# Sheet1.net
KiCad netlist of a schematic drawn in Altium Designer
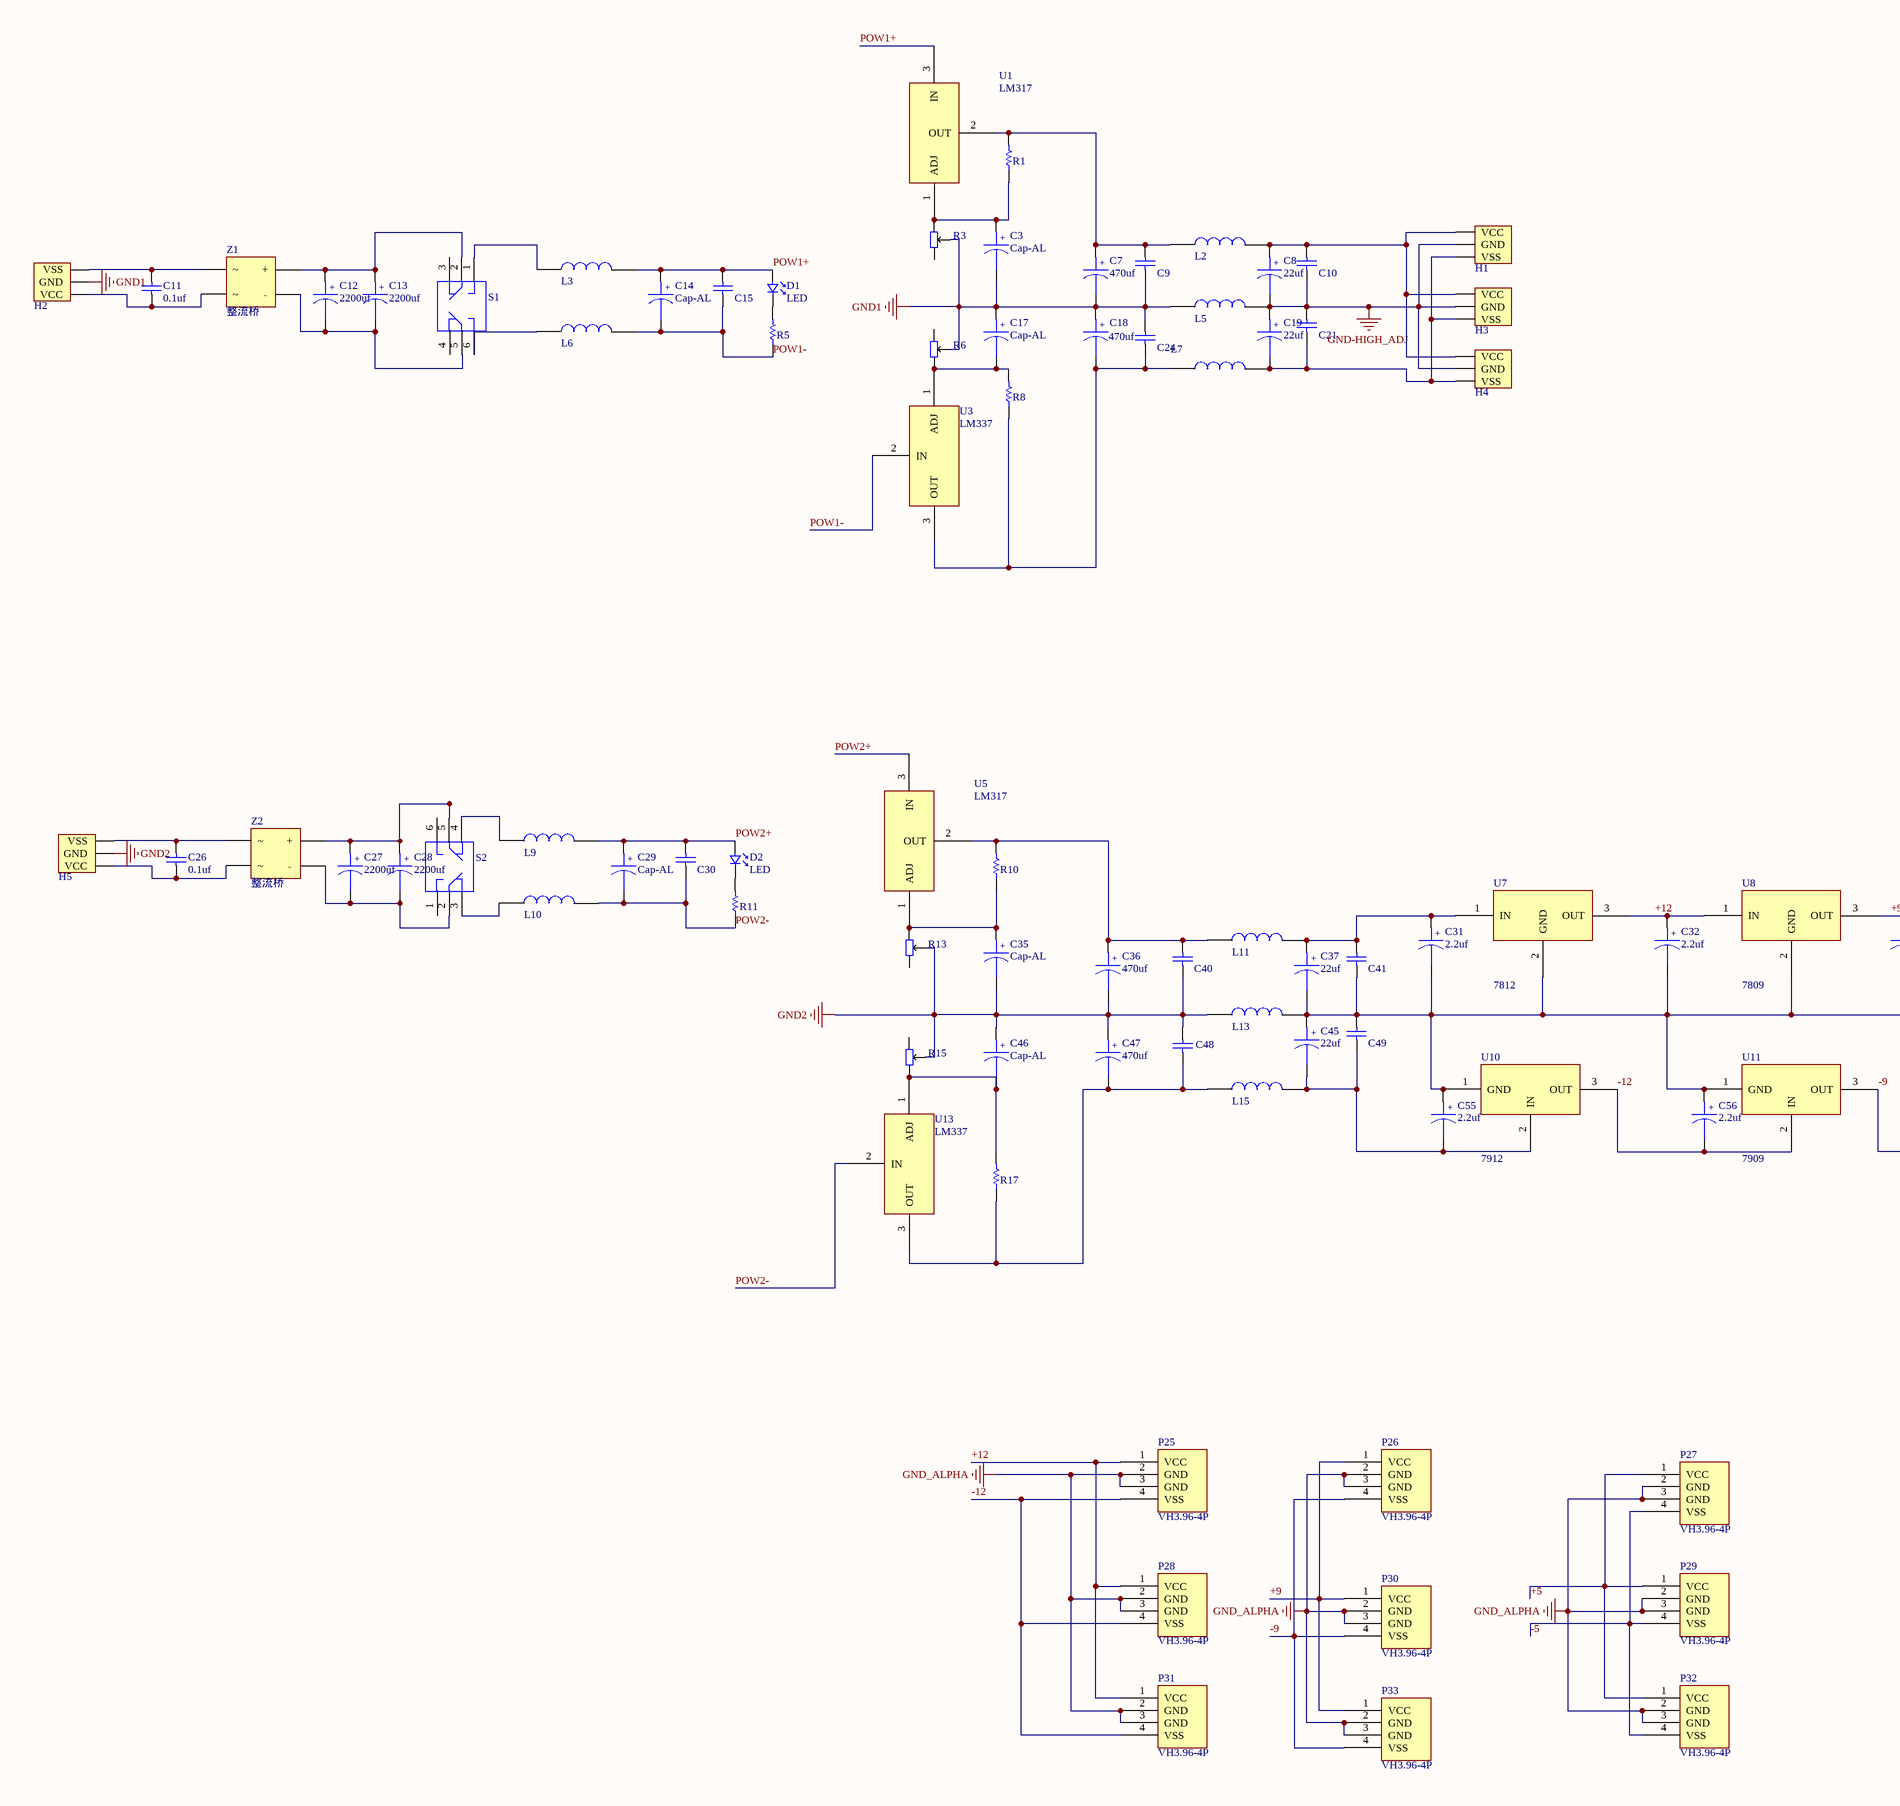
[diagram p0: Sheet1.SchDoc, left]
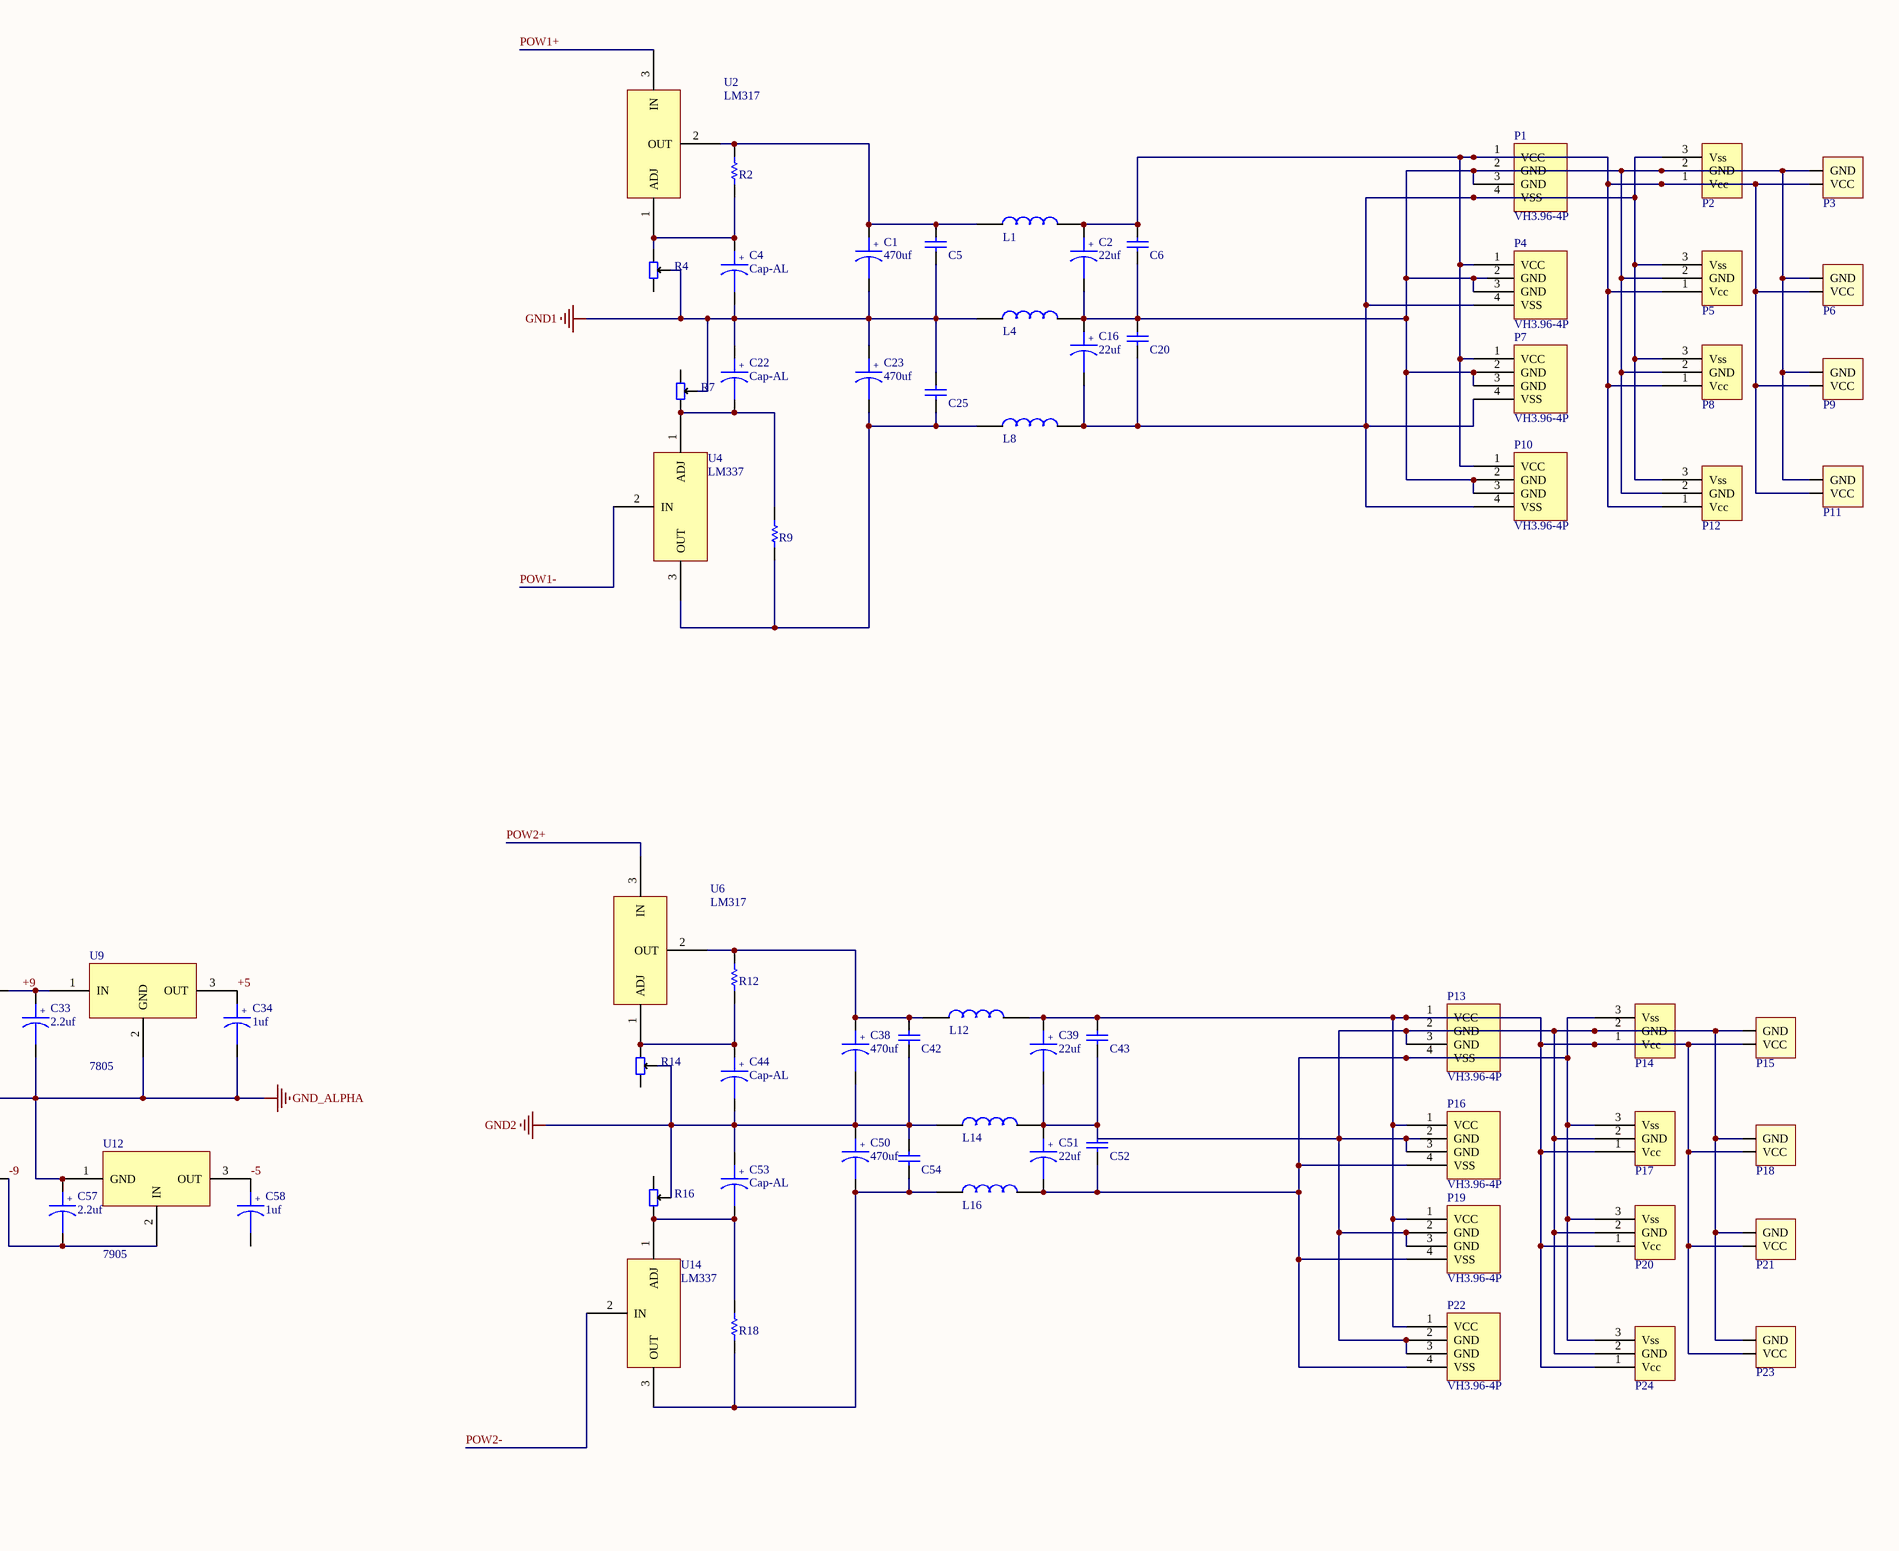
[diagram p1: Sheet1.SchDoc, right]

(export (version "E")
  (design (tool "Eeschema 10.0.6"))
  (components
    (comp (ref "C1") (value "470uf") (footprint "CD-5mm") (libsource (lib "电源") (part "Cap-AL")))
    (comp (ref "C2") (value "22uf") (footprint "CD-3mm") (libsource (lib "电源") (part "Cap-AL")))
    (comp (ref "C3") (value "Cap-AL") (footprint "CD-2.2mm") (libsource (lib "电源") (part "Cap-AL")))
    (comp (ref "C4") (value "Cap-AL") (footprint "CD-2.2mm") (libsource (lib "电源") (part "Cap-AL")))
    (comp (ref "C5") (value "Cap-SEMI") (footprint "独石电容") (libsource (lib "电源") (part "Cap-SEMI")))
    (comp (ref "C6") (value "Cap-SEMI") (footprint "独石电容") (libsource (lib "电源") (part "Cap-SEMI")))
    (comp (ref "C7") (value "470uf") (footprint "CD-5mm") (libsource (lib "电源") (part "Cap-AL")))
    (comp (ref "C8") (value "22uf") (footprint "CD-3mm") (libsource (lib "电源") (part "Cap-AL")))
    (comp (ref "C9") (value "Cap-SEMI") (footprint "独石电容") (libsource (lib "电源") (part "Cap-SEMI")))
    (comp (ref "C10") (value "Cap-SEMI") (footprint "独石电容") (libsource (lib "电源") (part "Cap-SEMI")))
    (comp (ref "C11")
      (value "Cap1")
      (footprint "安规电容")
      (fields (field (name "值") "0.1uf"))
      (libsource (lib "电源") (part "Cap1"))
    )
    (comp (ref "C12") (value "2200uf") (footprint "CD-7.6mm") (libsource (lib "电源") (part "Cap")))
    (comp (ref "C13") (value "2200uf") (footprint "CD-7.6mm") (libsource (lib "电源") (part "Cap")))
    (comp (ref "C14") (value "Cap-AL") (footprint "CD-3mm") (libsource (lib "电源") (part "Cap-AL")))
    (comp (ref "C15") (value "0.1uf") (footprint "独石电容") (libsource (lib "电源") (part "Cap-SEMI")))
    (comp (ref "C16") (value "22uf") (footprint "CD-3mm") (libsource (lib "电源") (part "Cap-AL")))
    (comp (ref "C17") (value "Cap-AL") (footprint "CD-2.2mm") (libsource (lib "电源") (part "Cap-AL")))
    (comp (ref "C18") (value "470uf") (footprint "CD-5mm") (libsource (lib "电源") (part "Cap-AL")))
    (comp (ref "C19") (value "22uf") (footprint "CD-3mm") (libsource (lib "电源") (part "Cap-AL")))
    (comp (ref "C20") (value "Cap-SEMI") (footprint "独石电容") (libsource (lib "电源") (part "Cap-SEMI")))
    (comp (ref "C21") (value "Cap-SEMI") (footprint "独石电容") (libsource (lib "电源") (part "Cap-SEMI")))
    (comp (ref "C22") (value "Cap-AL") (footprint "CD-2.2mm") (libsource (lib "电源") (part "Cap-AL")))
    (comp (ref "C23") (value "470uf") (footprint "CD-5mm") (libsource (lib "电源") (part "Cap-AL")))
    (comp (ref "C24") (value "Cap-SEMI") (footprint "独石电容") (libsource (lib "电源") (part "Cap-SEMI")))
    (comp (ref "C25") (value "Cap-SEMI") (footprint "独石电容") (libsource (lib "电源") (part "Cap-SEMI")))
    (comp (ref "C26")
      (value "Cap1")
      (footprint "安规电容")
      (fields (field (name "值") "0.1uf"))
      (libsource (lib "电源") (part "Cap1"))
    )
    (comp (ref "C27") (value "2200uf") (footprint "CD-7.6mm") (libsource (lib "电源") (part "Cap")))
    (comp (ref "C28") (value "2200uf") (footprint "CD-7.6mm") (libsource (lib "电源") (part "Cap")))
    (comp (ref "C29") (value "Cap-AL") (footprint "CD-3mm") (libsource (lib "电源") (part "Cap-AL")))
    (comp (ref "C30") (value "0.1uf") (footprint "独石电容") (libsource (lib "电源") (part "Cap-SEMI")))
    (comp (ref "C31") (value "2.2uf") (footprint "CD-2.2mm") (libsource (lib "电源") (part "Cap-AL")))
    (comp (ref "C32") (value "2.2uf") (footprint "CD-2.2mm") (libsource (lib "电源") (part "Cap-AL")))
    (comp (ref "C33") (value "2.2uf") (footprint "CD-2.2mm") (libsource (lib "电源") (part "Cap-AL")))
    (comp (ref "C34") (value "1uf") (footprint "CD-2.2mm") (libsource (lib "电源") (part "Cap-AL")))
    (comp (ref "C35") (value "Cap-AL") (footprint "CD-2.2mm") (libsource (lib "电源") (part "Cap-AL")))
    (comp (ref "C36") (value "470uf") (footprint "CD-5mm") (libsource (lib "电源") (part "Cap-AL")))
    (comp (ref "C37") (value "22uf") (footprint "CD-3mm") (libsource (lib "电源") (part "Cap-AL")))
    (comp (ref "C38") (value "470uf") (footprint "CD-5mm") (libsource (lib "电源") (part "Cap-AL")))
    (comp (ref "C39") (value "22uf") (footprint "CD-3mm") (libsource (lib "电源") (part "Cap-AL")))
    (comp (ref "C40") (value "Cap-SEMI") (footprint "独石电容") (libsource (lib "电源") (part "Cap-SEMI")))
    (comp (ref "C41") (value "Cap-SEMI") (footprint "独石电容") (libsource (lib "电源") (part "Cap-SEMI")))
    (comp (ref "C42") (value "Cap-SEMI") (footprint "独石电容") (libsource (lib "电源") (part "Cap-SEMI")))
    (comp (ref "C43") (value "Cap-SEMI") (footprint "独石电容") (libsource (lib "电源") (part "Cap-SEMI")))
    (comp (ref "C44") (value "Cap-AL") (footprint "CD-2.2mm") (libsource (lib "电源") (part "Cap-AL")))
    (comp (ref "C45") (value "22uf") (footprint "CD-3mm") (libsource (lib "电源") (part "Cap-AL")))
    (comp (ref "C46") (value "Cap-AL") (footprint "CD-2.2mm") (libsource (lib "电源") (part "Cap-AL")))
    (comp (ref "C47") (value "470uf") (footprint "CD-5mm") (libsource (lib "电源") (part "Cap-AL")))
    (comp (ref "C48") (value "Cap-SEMI") (footprint "独石电容") (libsource (lib "电源") (part "Cap-SEMI")))
    (comp (ref "C49") (value "Cap-SEMI") (footprint "独石电容") (libsource (lib "电源") (part "Cap-SEMI")))
    (comp (ref "C50") (value "470uf") (footprint "CD-5mm") (libsource (lib "电源") (part "Cap-AL")))
    (comp (ref "C51") (value "22uf") (footprint "CD-3mm") (libsource (lib "电源") (part "Cap-AL")))
    (comp (ref "C52") (value "Cap-SEMI") (footprint "独石电容") (libsource (lib "电源") (part "Cap-SEMI")))
    (comp (ref "C53") (value "Cap-AL") (footprint "CD-2.2mm") (libsource (lib "电源") (part "Cap-AL")))
    (comp (ref "C54") (value "Cap-SEMI") (footprint "独石电容") (libsource (lib "电源") (part "Cap-SEMI")))
    (comp (ref "C55") (value "2.2uf") (footprint "CD-2.2mm") (libsource (lib "电源") (part "Cap-AL")))
    (comp (ref "C56") (value "2.2uf") (footprint "CD-2.2mm") (libsource (lib "电源") (part "Cap-AL")))
    (comp (ref "C57") (value "2.2uf") (footprint "CD-2.2mm") (libsource (lib "电源") (part "Cap-AL")))
    (comp (ref "C58") (value "1uf") (footprint "CD-2.2mm") (libsource (lib "电源") (part "Cap-AL")))
    (comp (ref "D1") (value "LED") (footprint "0805_s") (libsource (lib "电源") (part "LED")))
    (comp (ref "D2") (value "LED") (footprint "0805_s") (libsource (lib "电源") (part "LED")))
    (comp (ref "H1")
      (value "KF128-5.08-3P")
      (footprint "KF128-5.08-3P")
      (libsource (lib "电源") (part "KF128-5.08-3P"))
    )
    (comp (ref "H2")
      (value "KF128-5.08-3P")
      (footprint "KF128-5.08-3P")
      (libsource (lib "") (part "KF128-5.08-3P_1"))
    )
    (comp (ref "H3")
      (value "KF128-5.08-3P")
      (footprint "KF128-5.08-3P")
      (libsource (lib "电源") (part "KF128-5.08-3P"))
    )
    (comp (ref "H4")
      (value "KF128-5.08-3P")
      (footprint "KF128-5.08-3P")
      (libsource (lib "电源") (part "KF128-5.08-3P"))
    )
    (comp (ref "H5")
      (value "KF128-5.08-3P")
      (footprint "KF128-5.08-3P")
      (libsource (lib "") (part "KF128-5.08-3P_1"))
    )
    (comp (ref "L1") (value "SMD") (footprint "功率电感-12x12 - duplicate") (libsource (lib "电源") (part "功率电感")))
    (comp (ref "L2") (value "SMD") (footprint "功率电感-12x12 - duplicate") (libsource (lib "电源") (part "功率电感")))
    (comp (ref "L3") (value "SMD") (footprint "功率电感-12x12 - duplicate") (libsource (lib "电源") (part "功率电感")))
    (comp (ref "L4") (value "SMD") (footprint "功率电感-12x12 - duplicate") (libsource (lib "电源") (part "功率电感")))
    (comp (ref "L5") (value "SMD") (footprint "功率电感-12x12 - duplicate") (libsource (lib "电源") (part "功率电感")))
    (comp (ref "L6") (value "SMD") (footprint "功率电感-12x12 - duplicate") (libsource (lib "电源") (part "功率电感")))
    (comp (ref "L7") (value "SMD") (footprint "功率电感-12x12 - duplicate") (libsource (lib "电源") (part "功率电感")))
    (comp (ref "L8") (value "SMD") (footprint "功率电感-12x12 - duplicate") (libsource (lib "电源") (part "功率电感")))
    (comp (ref "L9") (value "SMD") (footprint "功率电感-12x12 - duplicate") (libsource (lib "电源") (part "功率电感")))
    (comp (ref "L10") (value "SMD") (footprint "功率电感-12x12 - duplicate") (libsource (lib "电源") (part "功率电感")))
    (comp (ref "L11") (value "SMD") (footprint "功率电感-12x12 - duplicate") (libsource (lib "电源") (part "功率电感")))
    (comp (ref "L12") (value "SMD") (footprint "功率电感-12x12 - duplicate") (libsource (lib "电源") (part "功率电感")))
    (comp (ref "L13") (value "SMD") (footprint "功率电感-12x12 - duplicate") (libsource (lib "电源") (part "功率电感")))
    (comp (ref "L14") (value "SMD") (footprint "功率电感-12x12 - duplicate") (libsource (lib "电源") (part "功率电感")))
    (comp (ref "L15") (value "SMD") (footprint "功率电感-12x12 - duplicate") (libsource (lib "电源") (part "功率电感")))
    (comp (ref "L16") (value "SMD") (footprint "功率电感-12x12 - duplicate") (libsource (lib "电源") (part "功率电感")))
    (comp (ref "P1") (value "VH3.96-4P") (footprint "VH3.96-4P") (libsource (lib "电源") (part "VH3.96-4P")))
    (comp (ref "P2") (value "XH2.54-3p") (footprint "XH2.54-3p") (libsource (lib "电源") (part "XH2.54-3p")))
    (comp (ref "P3")
      (value "Power_2Port")
      (footprint "Power_S_2Port")
      (libsource (lib "电源") (part "Power_2Port"))
    )
    (comp (ref "P4") (value "VH3.96-4P") (footprint "VH3.96-4P") (libsource (lib "电源") (part "VH3.96-4P")))
    (comp (ref "P5") (value "XH2.54-3p") (footprint "XH2.54-3p") (libsource (lib "电源") (part "XH2.54-3p")))
    (comp (ref "P6")
      (value "Power_2Port")
      (footprint "Power_S_2Port")
      (libsource (lib "电源") (part "Power_2Port"))
    )
    (comp (ref "P7") (value "VH3.96-4P") (footprint "VH3.96-4P") (libsource (lib "电源") (part "VH3.96-4P")))
    (comp (ref "P8") (value "XH2.54-3p") (footprint "XH2.54-3p") (libsource (lib "电源") (part "XH2.54-3p")))
    (comp (ref "P9")
      (value "Power_2Port")
      (footprint "Power_S_2Port")
      (libsource (lib "电源") (part "Power_2Port"))
    )
    (comp (ref "P10") (value "VH3.96-4P") (footprint "VH3.96-4P") (libsource (lib "电源") (part "VH3.96-4P")))
    (comp (ref "P11")
      (value "Power_2Port")
      (footprint "Power_S_2Port")
      (libsource (lib "电源") (part "Power_2Port"))
    )
    (comp (ref "P12") (value "XH2.54-3p") (footprint "XH2.54-3p") (libsource (lib "电源") (part "XH2.54-3p")))
    (comp (ref "P13") (value "VH3.96-4P") (footprint "VH3.96-4P") (libsource (lib "电源") (part "VH3.96-4P")))
    (comp (ref "P14") (value "XH2.54-3p") (footprint "XH2.54-3p") (libsource (lib "电源") (part "XH2.54-3p")))
    (comp (ref "P15")
      (value "Power_2Port")
      (footprint "Power_S_2Port")
      (libsource (lib "电源") (part "Power_2Port"))
    )
    (comp (ref "P16") (value "VH3.96-4P") (footprint "VH3.96-4P") (libsource (lib "电源") (part "VH3.96-4P")))
    (comp (ref "P17") (value "XH2.54-3p") (footprint "XH2.54-3p") (libsource (lib "电源") (part "XH2.54-3p")))
    (comp (ref "P18")
      (value "Power_2Port")
      (footprint "Power_S_2Port")
      (libsource (lib "电源") (part "Power_2Port"))
    )
    (comp (ref "P19") (value "VH3.96-4P") (footprint "VH3.96-4P") (libsource (lib "电源") (part "VH3.96-4P")))
    (comp (ref "P20") (value "XH2.54-3p") (footprint "XH2.54-3p") (libsource (lib "电源") (part "XH2.54-3p")))
    (comp (ref "P21")
      (value "Power_2Port")
      (footprint "Power_S_2Port")
      (libsource (lib "电源") (part "Power_2Port"))
    )
    (comp (ref "P22") (value "VH3.96-4P") (footprint "VH3.96-4P") (libsource (lib "电源") (part "VH3.96-4P")))
    (comp (ref "P23")
      (value "Power_2Port")
      (footprint "Power_S_2Port")
      (libsource (lib "电源") (part "Power_2Port"))
    )
    (comp (ref "P24") (value "XH2.54-3p") (footprint "XH2.54-3p") (libsource (lib "电源") (part "XH2.54-3p")))
    (comp (ref "P25") (value "VH3.96-4P") (footprint "VH3.96-4P") (libsource (lib "电源") (part "VH3.96-4P")))
    (comp (ref "P26") (value "VH3.96-4P") (footprint "VH3.96-4P") (libsource (lib "电源") (part "VH3.96-4P")))
    (comp (ref "P27") (value "VH3.96-4P") (footprint "VH3.96-4P") (libsource (lib "电源") (part "VH3.96-4P")))
    (comp (ref "P28") (value "VH3.96-4P") (footprint "VH3.96-4P") (libsource (lib "电源") (part "VH3.96-4P")))
    (comp (ref "P29") (value "VH3.96-4P") (footprint "VH3.96-4P") (libsource (lib "电源") (part "VH3.96-4P")))
    (comp (ref "P30") (value "VH3.96-4P") (footprint "VH3.96-4P") (libsource (lib "电源") (part "VH3.96-4P")))
    (comp (ref "P31") (value "VH3.96-4P") (footprint "VH3.96-4P") (libsource (lib "电源") (part "VH3.96-4P")))
    (comp (ref "P32") (value "VH3.96-4P") (footprint "VH3.96-4P") (libsource (lib "电源") (part "VH3.96-4P")))
    (comp (ref "P33") (value "VH3.96-4P") (footprint "VH3.96-4P") (libsource (lib "电源") (part "VH3.96-4P")))
    (comp (ref "R1") (value "RES") (footprint "0805") (libsource (lib "电源") (part "RES")))
    (comp (ref "R2") (value "RES") (footprint "0805") (libsource (lib "电源") (part "RES")))
    (comp (ref "R3") (value "可调电位器1") (footprint "电位器") (libsource (lib "电源") (part "可调电位器1")))
    (comp (ref "R4") (value "可调电位器1") (footprint "电位器") (libsource (lib "电源") (part "可调电位器1")))
    (comp (ref "R5") (value "RES") (footprint "0805") (libsource (lib "电源") (part "RES")))
    (comp (ref "R6") (value "可调电位器1") (footprint "电位器") (libsource (lib "电源") (part "可调电位器1")))
    (comp (ref "R7") (value "可调电位器1") (footprint "电位器") (libsource (lib "电源") (part "可调电位器1")))
    (comp (ref "R8") (value "RES") (footprint "0805") (libsource (lib "电源") (part "RES")))
    (comp (ref "R9") (value "RES") (footprint "0805") (libsource (lib "电源") (part "RES")))
    (comp (ref "R10") (value "RES") (footprint "0805") (libsource (lib "电源") (part "RES")))
    (comp (ref "R11") (value "RES") (footprint "0805") (libsource (lib "电源") (part "RES")))
    (comp (ref "R12") (value "RES") (footprint "0805") (libsource (lib "电源") (part "RES")))
    (comp (ref "R13") (value "可调电位器1") (footprint "电位器") (libsource (lib "电源") (part "可调电位器1")))
    (comp (ref "R14") (value "可调电位器1") (footprint "电位器") (libsource (lib "电源") (part "可调电位器1")))
    (comp (ref "R15") (value "可调电位器1") (footprint "电位器") (libsource (lib "电源") (part "可调电位器1")))
    (comp (ref "R16") (value "可调电位器1") (footprint "电位器") (libsource (lib "电源") (part "可调电位器1")))
    (comp (ref "R17") (value "RES") (footprint "0805") (libsource (lib "电源") (part "RES")))
    (comp (ref "R18") (value "RES") (footprint "0805") (libsource (lib "电源") (part "RES")))
    (comp (ref "S1") (value "双掷开关") (footprint "SWITCH") (libsource (lib "电源") (part "双掷开关")))
    (comp (ref "S2") (value "双掷开关") (footprint "SWITCH") (libsource (lib "电源") (part "双掷开关")))
    (comp (ref "U1") (value "LM317") (footprint "TO-220") (libsource (lib "电源") (part "LM317")))
    (comp (ref "U2") (value "LM317") (footprint "TO-220") (libsource (lib "电源") (part "LM317")))
    (comp (ref "U3") (value "LM337") (footprint "TO-220") (libsource (lib "电源") (part "LM337")))
    (comp (ref "U4") (value "LM337") (footprint "TO-220") (libsource (lib "电源") (part "LM337")))
    (comp (ref "U5") (value "LM317") (footprint "TO-220") (libsource (lib "电源") (part "LM317")))
    (comp (ref "U6") (value "LM317") (footprint "TO-220") (libsource (lib "电源") (part "LM317")))
    (comp (ref "U7") (value "7812") (footprint "TO-220") (libsource (lib "电源") (part "78XX")))
    (comp (ref "U8") (value "7809") (footprint "TO-220") (libsource (lib "电源") (part "78XX")))
    (comp (ref "U9") (value "7805") (footprint "TO-220") (libsource (lib "电源") (part "78XX")))
    (comp (ref "U10") (value "7912") (footprint "TO-220") (libsource (lib "电源") (part "79XX")))
    (comp (ref "U11") (value "7909") (footprint "TO-220") (libsource (lib "电源") (part "79XX")))
    (comp (ref "U12") (value "7905") (footprint "TO-220") (libsource (lib "电源") (part "79XX")))
    (comp (ref "U13") (value "LM337") (footprint "TO-220") (libsource (lib "电源") (part "LM337")))
    (comp (ref "U14") (value "LM337") (footprint "TO-220") (libsource (lib "电源") (part "LM337")))
    (comp (ref "Z1") (value "整流桥") (footprint "整流桥") (libsource (lib "电源") (part "整流桥")))
    (comp (ref "Z2") (value "整流桥") (footprint "整流桥") (libsource (lib "电源") (part "整流桥")))
  )
  (nets
    (net (code "1") (name "/+5") (class "Default")
      (node (ref "C34") (pin "1") (pinfunction "1_1") (pintype "passive"))
      (node (ref "P27") (pin "1") (pinfunction "VCC_1") (pintype "passive"))
      (node (ref "P29") (pin "1") (pinfunction "VCC_1") (pintype "passive"))
      (node (ref "P32") (pin "1") (pinfunction "VCC_1") (pintype "passive"))
      (node (ref "U9") (pin "3") (pinfunction "OUT_3") (pintype "passive"))
    )
    (net (code "2") (name "/+9") (class "Default")
      (node (ref "C33") (pin "1") (pinfunction "1_1") (pintype "passive"))
      (node (ref "P26") (pin "1") (pinfunction "VCC_1") (pintype "passive"))
      (node (ref "P30") (pin "1") (pinfunction "VCC_1") (pintype "passive"))
      (node (ref "P33") (pin "1") (pinfunction "VCC_1") (pintype "passive"))
      (node (ref "U8") (pin "3") (pinfunction "OUT_3") (pintype "passive"))
      (node (ref "U9") (pin "1") (pinfunction "IN_1") (pintype "passive"))
    )
    (net (code "3") (name "/+12") (class "Default")
      (node (ref "C32") (pin "1") (pinfunction "1_1") (pintype "passive"))
      (node (ref "P25") (pin "1") (pinfunction "VCC_1") (pintype "passive"))
      (node (ref "P28") (pin "1") (pinfunction "VCC_1") (pintype "passive"))
      (node (ref "P31") (pin "1") (pinfunction "VCC_1") (pintype "passive"))
      (node (ref "U7") (pin "3") (pinfunction "OUT_3") (pintype "passive"))
      (node (ref "U8") (pin "1") (pinfunction "IN_1") (pintype "passive"))
    )
    (net (code "4") (name "/-5") (class "Default")
      (node (ref "C58") (pin "1") (pinfunction "1_1") (pintype "passive"))
      (node (ref "P27") (pin "4") (pinfunction "VSS_4") (pintype "passive"))
      (node (ref "P29") (pin "4") (pinfunction "VSS_4") (pintype "passive"))
      (node (ref "P32") (pin "4") (pinfunction "VSS_4") (pintype "passive"))
      (node (ref "U12") (pin "3") (pinfunction "OUT_3") (pintype "passive"))
    )
    (net (code "5") (name "/-9") (class "Default")
      (node (ref "C57") (pin "2") (pinfunction "2_2") (pintype "passive"))
      (node (ref "P26") (pin "4") (pinfunction "VSS_4") (pintype "passive"))
      (node (ref "P30") (pin "4") (pinfunction "VSS_4") (pintype "passive"))
      (node (ref "P33") (pin "4") (pinfunction "VSS_4") (pintype "passive"))
      (node (ref "U11") (pin "3") (pinfunction "OUT_3") (pintype "passive"))
      (node (ref "U12") (pin "2") (pinfunction "IN_2") (pintype "passive"))
    )
    (net (code "6") (name "/-12") (class "Default")
      (node (ref "C56") (pin "2") (pinfunction "2_2") (pintype "passive"))
      (node (ref "P25") (pin "4") (pinfunction "VSS_4") (pintype "passive"))
      (node (ref "P28") (pin "4") (pinfunction "VSS_4") (pintype "passive"))
      (node (ref "P31") (pin "4") (pinfunction "VSS_4") (pintype "passive"))
      (node (ref "U10") (pin "3") (pinfunction "OUT_3") (pintype "passive"))
      (node (ref "U11") (pin "2") (pinfunction "IN_2") (pintype "passive"))
    )
    (net (code "7") (name "/POW1+") (class "Default")
      (node (ref "C14") (pin "1") (pinfunction "1_1") (pintype "passive"))
      (node (ref "C15") (pin "2") (pinfunction "2_2") (pintype "passive"))
      (node (ref "D1") (pin "2") (pinfunction "2_2") (pintype "passive"))
      (node (ref "L3") (pin "2") (pintype "passive"))
      (node (ref "U1") (pin "3") (pinfunction "IN_3") (pintype "passive"))
      (node (ref "U2") (pin "3") (pinfunction "IN_3") (pintype "passive"))
    )
    (net (code "8") (name "/POW1-") (class "Default")
      (node (ref "C14") (pin "2") (pinfunction "2_2") (pintype "passive"))
      (node (ref "C15") (pin "1") (pinfunction "1_1") (pintype "passive"))
      (node (ref "L6") (pin "2") (pintype "passive"))
      (node (ref "R5") (pin "1") (pinfunction "1_1") (pintype "passive"))
      (node (ref "U3") (pin "2") (pinfunction "IN_2") (pintype "passive"))
      (node (ref "U4") (pin "2") (pinfunction "IN_2") (pintype "passive"))
    )
    (net (code "9") (name "/POW2+") (class "Default")
      (node (ref "C29") (pin "1") (pinfunction "1_1") (pintype "passive"))
      (node (ref "C30") (pin "2") (pinfunction "2_2") (pintype "passive"))
      (node (ref "D2") (pin "2") (pinfunction "2_2") (pintype "passive"))
      (node (ref "L9") (pin "2") (pintype "passive"))
      (node (ref "U5") (pin "3") (pinfunction "IN_3") (pintype "passive"))
      (node (ref "U6") (pin "3") (pinfunction "IN_3") (pintype "passive"))
    )
    (net (code "10") (name "/POW2-") (class "Default")
      (node (ref "C29") (pin "2") (pinfunction "2_2") (pintype "passive"))
      (node (ref "C30") (pin "1") (pinfunction "1_1") (pintype "passive"))
      (node (ref "L10") (pin "2") (pintype "passive"))
      (node (ref "R11") (pin "1") (pinfunction "1_1") (pintype "passive"))
      (node (ref "U13") (pin "2") (pinfunction "IN_2") (pintype "passive"))
      (node (ref "U14") (pin "2") (pinfunction "IN_2") (pintype "passive"))
    )
    (net (code "11") (name "GND-HIGH_ADJ") (class "Default")
      (node (ref "C10") (pin "1") (pinfunction "1_1") (pintype "passive"))
      (node (ref "C19") (pin "1") (pinfunction "1_1") (pintype "passive"))
      (node (ref "C21") (pin "2") (pinfunction "2_2") (pintype "passive"))
      (node (ref "C8") (pin "2") (pinfunction "2_2") (pintype "passive"))
      (node (ref "H1") (pin "2") (pinfunction "GND_2") (pintype "passive"))
      (node (ref "H3") (pin "2") (pinfunction "GND_2") (pintype "passive"))
      (node (ref "H4") (pin "2") (pinfunction "GND_2") (pintype "passive"))
      (node (ref "L5") (pin "2") (pintype "passive"))
    )
    (net (code "12") (name "GND1") (class "Default")
      (node (ref "C1") (pin "2") (pinfunction "2_2") (pintype "passive"))
      (node (ref "C17") (pin "1") (pinfunction "1_1") (pintype "passive"))
      (node (ref "C18") (pin "1") (pinfunction "1_1") (pintype "passive"))
      (node (ref "C22") (pin "1") (pinfunction "1_1") (pintype "passive"))
      (node (ref "C23") (pin "1") (pinfunction "1_1") (pintype "passive"))
      (node (ref "C24") (pin "2") (pinfunction "2_2") (pintype "passive"))
      (node (ref "C25") (pin "2") (pinfunction "2_2") (pintype "passive"))
      (node (ref "C3") (pin "2") (pinfunction "2_2") (pintype "passive"))
      (node (ref "C4") (pin "2") (pinfunction "2_2") (pintype "passive"))
      (node (ref "C5") (pin "1") (pinfunction "1_1") (pintype "passive"))
      (node (ref "C7") (pin "2") (pinfunction "2_2") (pintype "passive"))
      (node (ref "C9") (pin "1") (pinfunction "1_1") (pintype "passive"))
      (node (ref "H2") (pin "2") (pinfunction "GND_2") (pintype "passive"))
      (node (ref "L4") (pin "1") (pintype "passive"))
      (node (ref "L5") (pin "1") (pintype "passive"))
      (node (ref "R3") (pin "2") (pinfunction "2_2") (pintype "passive"))
      (node (ref "R4") (pin "2") (pinfunction "2_2") (pintype "passive"))
      (node (ref "R6") (pin "2") (pinfunction "2_2") (pintype "passive"))
      (node (ref "R7") (pin "2") (pinfunction "2_2") (pintype "passive"))
    )
    (net (code "13") (name "GND2") (class "Default")
      (node (ref "C35") (pin "2") (pinfunction "2_2") (pintype "passive"))
      (node (ref "C36") (pin "2") (pinfunction "2_2") (pintype "passive"))
      (node (ref "C38") (pin "2") (pinfunction "2_2") (pintype "passive"))
      (node (ref "C40") (pin "1") (pinfunction "1_1") (pintype "passive"))
      (node (ref "C42") (pin "1") (pinfunction "1_1") (pintype "passive"))
      (node (ref "C44") (pin "2") (pinfunction "2_2") (pintype "passive"))
      (node (ref "C46") (pin "1") (pinfunction "1_1") (pintype "passive"))
      (node (ref "C47") (pin "1") (pinfunction "1_1") (pintype "passive"))
      (node (ref "C48") (pin "2") (pinfunction "2_2") (pintype "passive"))
      (node (ref "C50") (pin "1") (pinfunction "1_1") (pintype "passive"))
      (node (ref "C53") (pin "1") (pinfunction "1_1") (pintype "passive"))
      (node (ref "C54") (pin "2") (pinfunction "2_2") (pintype "passive"))
      (node (ref "H5") (pin "2") (pinfunction "GND_2") (pintype "passive"))
      (node (ref "L13") (pin "1") (pintype "passive"))
      (node (ref "L14") (pin "1") (pintype "passive"))
      (node (ref "R13") (pin "2") (pinfunction "2_2") (pintype "passive"))
      (node (ref "R14") (pin "2") (pinfunction "2_2") (pintype "passive"))
      (node (ref "R15") (pin "2") (pinfunction "2_2") (pintype "passive"))
      (node (ref "R16") (pin "2") (pinfunction "2_2") (pintype "passive"))
    )
    (net (code "14") (name "GND_ALPHA") (class "Default")
      (node (ref "C31") (pin "2") (pinfunction "2_2") (pintype "passive"))
      (node (ref "C32") (pin "2") (pinfunction "2_2") (pintype "passive"))
      (node (ref "C33") (pin "2") (pinfunction "2_2") (pintype "passive"))
      (node (ref "C34") (pin "2") (pinfunction "2_2") (pintype "passive"))
      (node (ref "C37") (pin "2") (pinfunction "2_2") (pintype "passive"))
      (node (ref "C41") (pin "1") (pinfunction "1_1") (pintype "passive"))
      (node (ref "C45") (pin "1") (pinfunction "1_1") (pintype "passive"))
      (node (ref "C49") (pin "2") (pinfunction "2_2") (pintype "passive"))
      (node (ref "C55") (pin "1") (pinfunction "1_1") (pintype "passive"))
      (node (ref "C56") (pin "1") (pinfunction "1_1") (pintype "passive"))
      (node (ref "C57") (pin "1") (pinfunction "1_1") (pintype "passive"))
      (node (ref "L13") (pin "2") (pintype "passive"))
      (node (ref "P25") (pin "2") (pinfunction "GND_2") (pintype "passive"))
      (node (ref "P25") (pin "3") (pinfunction "GND_3") (pintype "passive"))
      (node (ref "P26") (pin "2") (pinfunction "GND_2") (pintype "passive"))
      (node (ref "P26") (pin "3") (pinfunction "GND_3") (pintype "passive"))
      (node (ref "P27") (pin "2") (pinfunction "GND_2") (pintype "passive"))
      (node (ref "P27") (pin "3") (pinfunction "GND_3") (pintype "passive"))
      (node (ref "P28") (pin "2") (pinfunction "GND_2") (pintype "passive"))
      (node (ref "P28") (pin "3") (pinfunction "GND_3") (pintype "passive"))
      (node (ref "P29") (pin "2") (pinfunction "GND_2") (pintype "passive"))
      (node (ref "P29") (pin "3") (pinfunction "GND_3") (pintype "passive"))
      (node (ref "P30") (pin "2") (pinfunction "GND_2") (pintype "passive"))
      (node (ref "P30") (pin "3") (pinfunction "GND_3") (pintype "passive"))
      (node (ref "P31") (pin "2") (pinfunction "GND_2") (pintype "passive"))
      (node (ref "P31") (pin "3") (pinfunction "GND_3") (pintype "passive"))
      (node (ref "P32") (pin "2") (pinfunction "GND_2") (pintype "passive"))
      (node (ref "P32") (pin "3") (pinfunction "GND_3") (pintype "passive"))
      (node (ref "P33") (pin "2") (pinfunction "GND_2") (pintype "passive"))
      (node (ref "P33") (pin "3") (pinfunction "GND_3") (pintype "passive"))
      (node (ref "U10") (pin "1") (pinfunction "GND_1") (pintype "passive"))
      (node (ref "U11") (pin "1") (pinfunction "GND_1") (pintype "passive"))
      (node (ref "U12") (pin "1") (pinfunction "GND_1") (pintype "passive"))
      (node (ref "U7") (pin "2") (pinfunction "GND_2") (pintype "passive"))
      (node (ref "U8") (pin "2") (pinfunction "GND_2") (pintype "passive"))
      (node (ref "U9") (pin "2") (pinfunction "GND_2") (pintype "passive"))
    )
    (net (code "15") (name "Net-(D1-Pad1)") (class "Default")
      (node (ref "D1") (pin "1") (pinfunction "1_1") (pintype "passive"))
      (node (ref "R5") (pin "2") (pinfunction "2_2") (pintype "passive"))
    )
    (net (code "16") (name "Net-(D2-Pad1)") (class "Default")
      (node (ref "D2") (pin "1") (pinfunction "1_1") (pintype "passive"))
      (node (ref "R11") (pin "2") (pinfunction "2_2") (pintype "passive"))
    )
    (net (code "17") (name "Net-(H1-VCC)") (class "Default")
      (node (ref "C10") (pin "2") (pinfunction "2_2") (pintype "passive"))
      (node (ref "C8") (pin "1") (pinfunction "1_1") (pintype "passive"))
      (node (ref "H1") (pin "1") (pinfunction "VCC_1") (pintype "passive"))
      (node (ref "H3") (pin "1") (pinfunction "VCC_1") (pintype "passive"))
      (node (ref "H4") (pin "1") (pinfunction "VCC_1") (pintype "passive"))
      (node (ref "L2") (pin "2") (pintype "passive"))
    )
    (net (code "18") (name "Net-(H1-VSS)") (class "Default")
      (node (ref "C19") (pin "2") (pinfunction "2_2") (pintype "passive"))
      (node (ref "C21") (pin "1") (pinfunction "1_1") (pintype "passive"))
      (node (ref "H1") (pin "3") (pinfunction "VSS_3") (pintype "passive"))
      (node (ref "H3") (pin "3") (pinfunction "VSS_3") (pintype "passive"))
      (node (ref "H4") (pin "3") (pinfunction "VSS_3") (pintype "passive"))
      (node (ref "L7") (pin "2") (pintype "passive"))
    )
    (net (code "19") (name "Net-(H2-VCC)") (class "Default")
      (node (ref "C11") (pin "1") (pinfunction "1_1") (pintype "passive"))
      (node (ref "H2") (pin "1") (pinfunction "VCC_1") (pintype "passive"))
      (node (ref "Z1") (pin "3") (pinfunction "~_3") (pintype "passive"))
    )
    (net (code "20") (name "Net-(H2-VSS)") (class "Default")
      (node (ref "C11") (pin "2") (pinfunction "2_2") (pintype "passive"))
      (node (ref "H2") (pin "3") (pinfunction "VSS_3") (pintype "passive"))
      (node (ref "Z1") (pin "2") (pinfunction "~_2") (pintype "passive"))
    )
    (net (code "21") (name "Net-(H5-VCC)") (class "Default")
      (node (ref "C26") (pin "1") (pinfunction "1_1") (pintype "passive"))
      (node (ref "H5") (pin "1") (pinfunction "VCC_1") (pintype "passive"))
      (node (ref "Z2") (pin "3") (pinfunction "~_3") (pintype "passive"))
    )
    (net (code "22") (name "Net-(H5-VSS)") (class "Default")
      (node (ref "C26") (pin "2") (pinfunction "2_2") (pintype "passive"))
      (node (ref "H5") (pin "3") (pinfunction "VSS_3") (pintype "passive"))
      (node (ref "Z2") (pin "2") (pinfunction "~_2") (pintype "passive"))
    )
    (net (code "23") (name "Net-(L3-Pad1)") (class "Default")
      (node (ref "L3") (pin "1") (pintype "passive"))
      (node (ref "S1") (pin "1") (pinfunction "1_1") (pintype "passive"))
    )
    (net (code "24") (name "Net-(L6-Pad1)") (class "Default")
      (node (ref "L6") (pin "1") (pintype "passive"))
      (node (ref "S1") (pin "6") (pinfunction "6_6") (pintype "passive"))
    )
    (net (code "25") (name "Net-(L9-Pad1)") (class "Default")
      (node (ref "L9") (pin "1") (pintype "passive"))
      (node (ref "S2") (pin "4") (pinfunction "4_4") (pintype "passive"))
    )
    (net (code "26") (name "Net-(L10-Pad1)") (class "Default")
      (node (ref "L10") (pin "1") (pintype "passive"))
      (node (ref "S2") (pin "3") (pinfunction "3_3") (pintype "passive"))
    )
    (net (code "27") (name "Net-(P1-VCC)") (class "Default")
      (node (ref "C2") (pin "1") (pinfunction "1_1") (pintype "passive"))
      (node (ref "C6") (pin "2") (pinfunction "2_2") (pintype "passive"))
      (node (ref "L1") (pin "2") (pintype "passive"))
      (node (ref "P1") (pin "1") (pinfunction "VCC_1") (pintype "passive"))
      (node (ref "P10") (pin "1") (pinfunction "VCC_1") (pintype "passive"))
      (node (ref "P11") (pin "1") (pinfunction "VCC_1") (pintype "passive"))
      (node (ref "P12") (pin "1") (pinfunction "Vcc_1") (pintype "passive"))
      (node (ref "P2") (pin "1") (pinfunction "Vcc_1") (pintype "passive"))
      (node (ref "P3") (pin "1") (pinfunction "VCC_1") (pintype "passive"))
      (node (ref "P4") (pin "1") (pinfunction "VCC_1") (pintype "passive"))
      (node (ref "P5") (pin "1") (pinfunction "Vcc_1") (pintype "passive"))
      (node (ref "P6") (pin "1") (pinfunction "VCC_1") (pintype "passive"))
      (node (ref "P7") (pin "1") (pinfunction "VCC_1") (pintype "passive"))
      (node (ref "P8") (pin "1") (pinfunction "Vcc_1") (pintype "passive"))
      (node (ref "P9") (pin "1") (pinfunction "VCC_1") (pintype "passive"))
    )
    (net (code "28") (name "Net-(P1-VSS)") (class "Default")
      (node (ref "C16") (pin "2") (pinfunction "2_2") (pintype "passive"))
      (node (ref "C20") (pin "1") (pinfunction "1_1") (pintype "passive"))
      (node (ref "L8") (pin "2") (pintype "passive"))
      (node (ref "P1") (pin "4") (pinfunction "VSS_4") (pintype "passive"))
      (node (ref "P10") (pin "4") (pinfunction "VSS_4") (pintype "passive"))
      (node (ref "P12") (pin "3") (pinfunction "Vss_3") (pintype "passive"))
      (node (ref "P2") (pin "3") (pinfunction "Vss_3") (pintype "passive"))
      (node (ref "P4") (pin "4") (pinfunction "VSS_4") (pintype "passive"))
      (node (ref "P5") (pin "3") (pinfunction "Vss_3") (pintype "passive"))
      (node (ref "P7") (pin "4") (pinfunction "VSS_4") (pintype "passive"))
      (node (ref "P8") (pin "3") (pinfunction "Vss_3") (pintype "passive"))
    )
    (net (code "29") (name "Net-(P11-GND)") (class "Default")
      (node (ref "C16") (pin "1") (pinfunction "1_1") (pintype "passive"))
      (node (ref "C2") (pin "2") (pinfunction "2_2") (pintype "passive"))
      (node (ref "C20") (pin "2") (pinfunction "2_2") (pintype "passive"))
      (node (ref "C6") (pin "1") (pinfunction "1_1") (pintype "passive"))
      (node (ref "L4") (pin "2") (pintype "passive"))
      (node (ref "P1") (pin "2") (pinfunction "GND_2") (pintype "passive"))
      (node (ref "P1") (pin "3") (pinfunction "GND_3") (pintype "passive"))
      (node (ref "P10") (pin "2") (pinfunction "GND_2") (pintype "passive"))
      (node (ref "P10") (pin "3") (pinfunction "GND_3") (pintype "passive"))
      (node (ref "P11") (pin "2") (pinfunction "GND_2") (pintype "passive"))
      (node (ref "P12") (pin "2") (pinfunction "GND_2") (pintype "passive"))
      (node (ref "P2") (pin "2") (pinfunction "GND_2") (pintype "passive"))
      (node (ref "P3") (pin "2") (pinfunction "GND_2") (pintype "passive"))
      (node (ref "P4") (pin "2") (pinfunction "GND_2") (pintype "passive"))
      (node (ref "P4") (pin "3") (pinfunction "GND_3") (pintype "passive"))
      (node (ref "P5") (pin "2") (pinfunction "GND_2") (pintype "passive"))
      (node (ref "P6") (pin "2") (pinfunction "GND_2") (pintype "passive"))
      (node (ref "P7") (pin "2") (pinfunction "GND_2") (pintype "passive"))
      (node (ref "P7") (pin "3") (pinfunction "GND_3") (pintype "passive"))
      (node (ref "P8") (pin "2") (pinfunction "GND_2") (pintype "passive"))
      (node (ref "P9") (pin "2") (pinfunction "GND_2") (pintype "passive"))
    )
    (net (code "30") (name "Net-(P13-VCC)") (class "Default")
      (node (ref "C39") (pin "1") (pinfunction "1_1") (pintype "passive"))
      (node (ref "C43") (pin "2") (pinfunction "2_2") (pintype "passive"))
      (node (ref "L12") (pin "2") (pintype "passive"))
      (node (ref "P13") (pin "1") (pinfunction "VCC_1") (pintype "passive"))
      (node (ref "P14") (pin "1") (pinfunction "Vcc_1") (pintype "passive"))
      (node (ref "P15") (pin "1") (pinfunction "VCC_1") (pintype "passive"))
      (node (ref "P16") (pin "1") (pinfunction "VCC_1") (pintype "passive"))
      (node (ref "P17") (pin "1") (pinfunction "Vcc_1") (pintype "passive"))
      (node (ref "P18") (pin "1") (pinfunction "VCC_1") (pintype "passive"))
      (node (ref "P19") (pin "1") (pinfunction "VCC_1") (pintype "passive"))
      (node (ref "P20") (pin "1") (pinfunction "Vcc_1") (pintype "passive"))
      (node (ref "P21") (pin "1") (pinfunction "VCC_1") (pintype "passive"))
      (node (ref "P22") (pin "1") (pinfunction "VCC_1") (pintype "passive"))
      (node (ref "P23") (pin "1") (pinfunction "VCC_1") (pintype "passive"))
      (node (ref "P24") (pin "1") (pinfunction "Vcc_1") (pintype "passive"))
    )
    (net (code "31") (name "Net-(P13-VSS)") (class "Default")
      (node (ref "C51") (pin "2") (pinfunction "2_2") (pintype "passive"))
      (node (ref "C52") (pin "1") (pinfunction "1_1") (pintype "passive"))
      (node (ref "L16") (pin "2") (pintype "passive"))
      (node (ref "P13") (pin "4") (pinfunction "VSS_4") (pintype "passive"))
      (node (ref "P14") (pin "3") (pinfunction "Vss_3") (pintype "passive"))
      (node (ref "P16") (pin "4") (pinfunction "VSS_4") (pintype "passive"))
      (node (ref "P17") (pin "3") (pinfunction "Vss_3") (pintype "passive"))
      (node (ref "P19") (pin "4") (pinfunction "VSS_4") (pintype "passive"))
      (node (ref "P20") (pin "3") (pinfunction "Vss_3") (pintype "passive"))
      (node (ref "P22") (pin "4") (pinfunction "VSS_4") (pintype "passive"))
      (node (ref "P24") (pin "3") (pinfunction "Vss_3") (pintype "passive"))
    )
    (net (code "32") (name "Net-(P14-GND)") (class "Default")
      (node (ref "C39") (pin "2") (pinfunction "2_2") (pintype "passive"))
      (node (ref "C43") (pin "1") (pinfunction "1_1") (pintype "passive"))
      (node (ref "C51") (pin "1") (pinfunction "1_1") (pintype "passive"))
      (node (ref "C52") (pin "2") (pinfunction "2_2") (pintype "passive"))
      (node (ref "L14") (pin "2") (pintype "passive"))
      (node (ref "P13") (pin "2") (pinfunction "GND_2") (pintype "passive"))
      (node (ref "P13") (pin "3") (pinfunction "GND_3") (pintype "passive"))
      (node (ref "P14") (pin "2") (pinfunction "GND_2") (pintype "passive"))
      (node (ref "P15") (pin "2") (pinfunction "GND_2") (pintype "passive"))
      (node (ref "P16") (pin "2") (pinfunction "GND_2") (pintype "passive"))
      (node (ref "P16") (pin "3") (pinfunction "GND_3") (pintype "passive"))
      (node (ref "P17") (pin "2") (pinfunction "GND_2") (pintype "passive"))
      (node (ref "P18") (pin "2") (pinfunction "GND_2") (pintype "passive"))
      (node (ref "P19") (pin "2") (pinfunction "GND_2") (pintype "passive"))
      (node (ref "P19") (pin "3") (pinfunction "GND_3") (pintype "passive"))
      (node (ref "P20") (pin "2") (pinfunction "GND_2") (pintype "passive"))
      (node (ref "P21") (pin "2") (pinfunction "GND_2") (pintype "passive"))
      (node (ref "P22") (pin "2") (pinfunction "GND_2") (pintype "passive"))
      (node (ref "P22") (pin "3") (pinfunction "GND_3") (pintype "passive"))
      (node (ref "P23") (pin "2") (pinfunction "GND_2") (pintype "passive"))
      (node (ref "P24") (pin "2") (pinfunction "GND_2") (pintype "passive"))
    )
    (net (code "33") (name "Net-(U1-ADJ)") (class "Default")
      (node (ref "C3") (pin "1") (pinfunction "1_1") (pintype "passive"))
      (node (ref "R1") (pin "1") (pinfunction "1_1") (pintype "passive"))
      (node (ref "R3") (pin "3") (pinfunction "3_3") (pintype "passive"))
      (node (ref "U1") (pin "1") (pinfunction "ADJ_1") (pintype "passive"))
    )
    (net (code "34") (name "Net-(U1-OUT)") (class "Default")
      (node (ref "C7") (pin "1") (pinfunction "1_1") (pintype "passive"))
      (node (ref "C9") (pin "2") (pinfunction "2_2") (pintype "passive"))
      (node (ref "L2") (pin "1") (pintype "passive"))
      (node (ref "R1") (pin "2") (pinfunction "2_2") (pintype "passive"))
      (node (ref "U1") (pin "2") (pinfunction "OUT_2") (pintype "passive"))
    )
    (net (code "35") (name "Net-(U2-ADJ)") (class "Default")
      (node (ref "C4") (pin "1") (pinfunction "1_1") (pintype "passive"))
      (node (ref "R2") (pin "1") (pinfunction "1_1") (pintype "passive"))
      (node (ref "R4") (pin "3") (pinfunction "3_3") (pintype "passive"))
      (node (ref "U2") (pin "1") (pinfunction "ADJ_1") (pintype "passive"))
    )
    (net (code "36") (name "Net-(U2-OUT)") (class "Default")
      (node (ref "C1") (pin "1") (pinfunction "1_1") (pintype "passive"))
      (node (ref "C5") (pin "2") (pinfunction "2_2") (pintype "passive"))
      (node (ref "L1") (pin "1") (pintype "passive"))
      (node (ref "R2") (pin "2") (pinfunction "2_2") (pintype "passive"))
      (node (ref "U2") (pin "2") (pinfunction "OUT_2") (pintype "passive"))
    )
    (net (code "37") (name "Net-(U3-ADJ)") (class "Default")
      (node (ref "C17") (pin "2") (pinfunction "2_2") (pintype "passive"))
      (node (ref "R6") (pin "1") (pinfunction "1_1") (pintype "passive"))
      (node (ref "R8") (pin "2") (pinfunction "2_2") (pintype "passive"))
      (node (ref "U3") (pin "1") (pinfunction "ADJ_1") (pintype "passive"))
    )
    (net (code "38") (name "Net-(U3-OUT)") (class "Default")
      (node (ref "C18") (pin "2") (pinfunction "2_2") (pintype "passive"))
      (node (ref "C24") (pin "1") (pinfunction "1_1") (pintype "passive"))
      (node (ref "L7") (pin "1") (pintype "passive"))
      (node (ref "R8") (pin "1") (pinfunction "1_1") (pintype "passive"))
      (node (ref "U3") (pin "3") (pinfunction "OUT_3") (pintype "passive"))
    )
    (net (code "39") (name "Net-(U4-ADJ)") (class "Default")
      (node (ref "C22") (pin "2") (pinfunction "2_2") (pintype "passive"))
      (node (ref "R7") (pin "1") (pinfunction "1_1") (pintype "passive"))
      (node (ref "R9") (pin "2") (pinfunction "2_2") (pintype "passive"))
      (node (ref "U4") (pin "1") (pinfunction "ADJ_1") (pintype "passive"))
    )
    (net (code "40") (name "Net-(U4-OUT)") (class "Default")
      (node (ref "C23") (pin "2") (pinfunction "2_2") (pintype "passive"))
      (node (ref "C25") (pin "1") (pinfunction "1_1") (pintype "passive"))
      (node (ref "L8") (pin "1") (pintype "passive"))
      (node (ref "R9") (pin "1") (pinfunction "1_1") (pintype "passive"))
      (node (ref "U4") (pin "3") (pinfunction "OUT_3") (pintype "passive"))
    )
    (net (code "41") (name "Net-(U5-ADJ)") (class "Default")
      (node (ref "C35") (pin "1") (pinfunction "1_1") (pintype "passive"))
      (node (ref "R10") (pin "1") (pinfunction "1_1") (pintype "passive"))
      (node (ref "R13") (pin "3") (pinfunction "3_3") (pintype "passive"))
      (node (ref "U5") (pin "1") (pinfunction "ADJ_1") (pintype "passive"))
    )
    (net (code "42") (name "Net-(U5-OUT)") (class "Default")
      (node (ref "C36") (pin "1") (pinfunction "1_1") (pintype "passive"))
      (node (ref "C40") (pin "2") (pinfunction "2_2") (pintype "passive"))
      (node (ref "L11") (pin "1") (pintype "passive"))
      (node (ref "R10") (pin "2") (pinfunction "2_2") (pintype "passive"))
      (node (ref "U5") (pin "2") (pinfunction "OUT_2") (pintype "passive"))
    )
    (net (code "43") (name "Net-(U6-ADJ)") (class "Default")
      (node (ref "C44") (pin "1") (pinfunction "1_1") (pintype "passive"))
      (node (ref "R12") (pin "1") (pinfunction "1_1") (pintype "passive"))
      (node (ref "R14") (pin "3") (pinfunction "3_3") (pintype "passive"))
      (node (ref "U6") (pin "1") (pinfunction "ADJ_1") (pintype "passive"))
    )
    (net (code "44") (name "Net-(U6-OUT)") (class "Default")
      (node (ref "C38") (pin "1") (pinfunction "1_1") (pintype "passive"))
      (node (ref "C42") (pin "2") (pinfunction "2_2") (pintype "passive"))
      (node (ref "L12") (pin "1") (pintype "passive"))
      (node (ref "R12") (pin "2") (pinfunction "2_2") (pintype "passive"))
      (node (ref "U6") (pin "2") (pinfunction "OUT_2") (pintype "passive"))
    )
    (net (code "45") (name "Net-(U7-IN)") (class "Default")
      (node (ref "C31") (pin "1") (pinfunction "1_1") (pintype "passive"))
      (node (ref "C37") (pin "1") (pinfunction "1_1") (pintype "passive"))
      (node (ref "C41") (pin "2") (pinfunction "2_2") (pintype "passive"))
      (node (ref "L11") (pin "2") (pintype "passive"))
      (node (ref "U7") (pin "1") (pinfunction "IN_1") (pintype "passive"))
    )
    (net (code "46") (name "Net-(U10-IN)") (class "Default")
      (node (ref "C45") (pin "2") (pinfunction "2_2") (pintype "passive"))
      (node (ref "C49") (pin "1") (pinfunction "1_1") (pintype "passive"))
      (node (ref "C55") (pin "2") (pinfunction "2_2") (pintype "passive"))
      (node (ref "L15") (pin "2") (pintype "passive"))
      (node (ref "U10") (pin "2") (pinfunction "IN_2") (pintype "passive"))
    )
    (net (code "47") (name "Net-(U13-ADJ)") (class "Default")
      (node (ref "C46") (pin "2") (pinfunction "2_2") (pintype "passive"))
      (node (ref "R15") (pin "1") (pinfunction "1_1") (pintype "passive"))
      (node (ref "R17") (pin "2") (pinfunction "2_2") (pintype "passive"))
      (node (ref "U13") (pin "1") (pinfunction "ADJ_1") (pintype "passive"))
    )
    (net (code "48") (name "Net-(U13-OUT)") (class "Default")
      (node (ref "C47") (pin "2") (pinfunction "2_2") (pintype "passive"))
      (node (ref "C48") (pin "1") (pinfunction "1_1") (pintype "passive"))
      (node (ref "L15") (pin "1") (pintype "passive"))
      (node (ref "R17") (pin "1") (pinfunction "1_1") (pintype "passive"))
      (node (ref "U13") (pin "3") (pinfunction "OUT_3") (pintype "passive"))
    )
    (net (code "49") (name "Net-(U14-ADJ)") (class "Default")
      (node (ref "C53") (pin "2") (pinfunction "2_2") (pintype "passive"))
      (node (ref "R16") (pin "1") (pinfunction "1_1") (pintype "passive"))
      (node (ref "R18") (pin "2") (pinfunction "2_2") (pintype "passive"))
      (node (ref "U14") (pin "1") (pinfunction "ADJ_1") (pintype "passive"))
    )
    (net (code "50") (name "Net-(U14-OUT)") (class "Default")
      (node (ref "C50") (pin "2") (pinfunction "2_2") (pintype "passive"))
      (node (ref "C54") (pin "1") (pinfunction "1_1") (pintype "passive"))
      (node (ref "L16") (pin "1") (pintype "passive"))
      (node (ref "R18") (pin "1") (pinfunction "1_1") (pintype "passive"))
      (node (ref "U14") (pin "3") (pinfunction "OUT_3") (pintype "passive"))
    )
    (net (code "51") (name "Net-(Z1-+)") (class "Default")
      (node (ref "C12") (pin "1") (pinfunction "1_1") (pintype "passive"))
      (node (ref "C13") (pin "1") (pinfunction "1_1") (pintype "passive"))
      (node (ref "S1") (pin "2") (pinfunction "2_2") (pintype "passive"))
      (node (ref "Z1") (pin "1") (pinfunction "+_1") (pintype "passive"))
    )
    (net (code "52") (name "Net-(Z1-﹣)") (class "Default")
      (node (ref "C12") (pin "2") (pinfunction "2_2") (pintype "passive"))
      (node (ref "C13") (pin "2") (pinfunction "2_2") (pintype "passive"))
      (node (ref "S1") (pin "5") (pinfunction "5_5") (pintype "passive"))
      (node (ref "Z1") (pin "4") (pinfunction "﹣_4") (pintype "passive"))
    )
    (net (code "53") (name "Net-(Z2-+)") (class "Default")
      (node (ref "C27") (pin "1") (pinfunction "1_1") (pintype "passive"))
      (node (ref "C28") (pin "1") (pinfunction "1_1") (pintype "passive"))
      (node (ref "S2") (pin "5") (pinfunction "5_5") (pintype "passive"))
      (node (ref "Z2") (pin "1") (pinfunction "+_1") (pintype "passive"))
    )
    (net (code "54") (name "Net-(Z2-﹣)") (class "Default")
      (node (ref "C27") (pin "2") (pinfunction "2_2") (pintype "passive"))
      (node (ref "C28") (pin "2") (pinfunction "2_2") (pintype "passive"))
      (node (ref "S2") (pin "2") (pinfunction "2_2") (pintype "passive"))
      (node (ref "Z2") (pin "4") (pinfunction "﹣_4") (pintype "passive"))
    )
    (net (code "55") (name "unconnected-(C58-Pad2)") (class "Default")
      (node (ref "C58") (pin "2") (pinfunction "2_2") (pintype "passive"))
    )
    (net (code "56") (name "unconnected-(R3-Pad1)") (class "Default")
      (node (ref "R3") (pin "1") (pinfunction "1_1") (pintype "passive"))
    )
    (net (code "57") (name "unconnected-(R4-Pad1)") (class "Default")
      (node (ref "R4") (pin "1") (pinfunction "1_1") (pintype "passive"))
    )
    (net (code "58") (name "unconnected-(R6-Pad3)") (class "Default")
      (node (ref "R6") (pin "3") (pinfunction "3_3") (pintype "passive"))
    )
    (net (code "59") (name "unconnected-(R7-Pad3)") (class "Default")
      (node (ref "R7") (pin "3") (pinfunction "3_3") (pintype "passive"))
    )
    (net (code "60") (name "unconnected-(R13-Pad1)") (class "Default")
      (node (ref "R13") (pin "1") (pinfunction "1_1") (pintype "passive"))
    )
    (net (code "61") (name "unconnected-(R14-Pad1)") (class "Default")
      (node (ref "R14") (pin "1") (pinfunction "1_1") (pintype "passive"))
    )
    (net (code "62") (name "unconnected-(R15-Pad3)") (class "Default")
      (node (ref "R15") (pin "3") (pinfunction "3_3") (pintype "passive"))
    )
    (net (code "63") (name "unconnected-(R16-Pad3)") (class "Default")
      (node (ref "R16") (pin "3") (pinfunction "3_3") (pintype "passive"))
    )
    (net (code "64") (name "unconnected-(S1-Pad3)") (class "Default")
      (node (ref "S1") (pin "3") (pinfunction "3_3") (pintype "passive"))
    )
    (net (code "65") (name "unconnected-(S1-Pad4)") (class "Default")
      (node (ref "S1") (pin "4") (pinfunction "4_4") (pintype "passive"))
    )
    (net (code "66") (name "unconnected-(S2-Pad1)") (class "Default")
      (node (ref "S2") (pin "1") (pinfunction "1_1") (pintype "passive"))
    )
    (net (code "67") (name "unconnected-(S2-Pad6)") (class "Default")
      (node (ref "S2") (pin "6") (pinfunction "6_6") (pintype "passive"))
    )
  )
)
